# Audio.net
KiCad netlist of a schematic drawn in Altium Designer
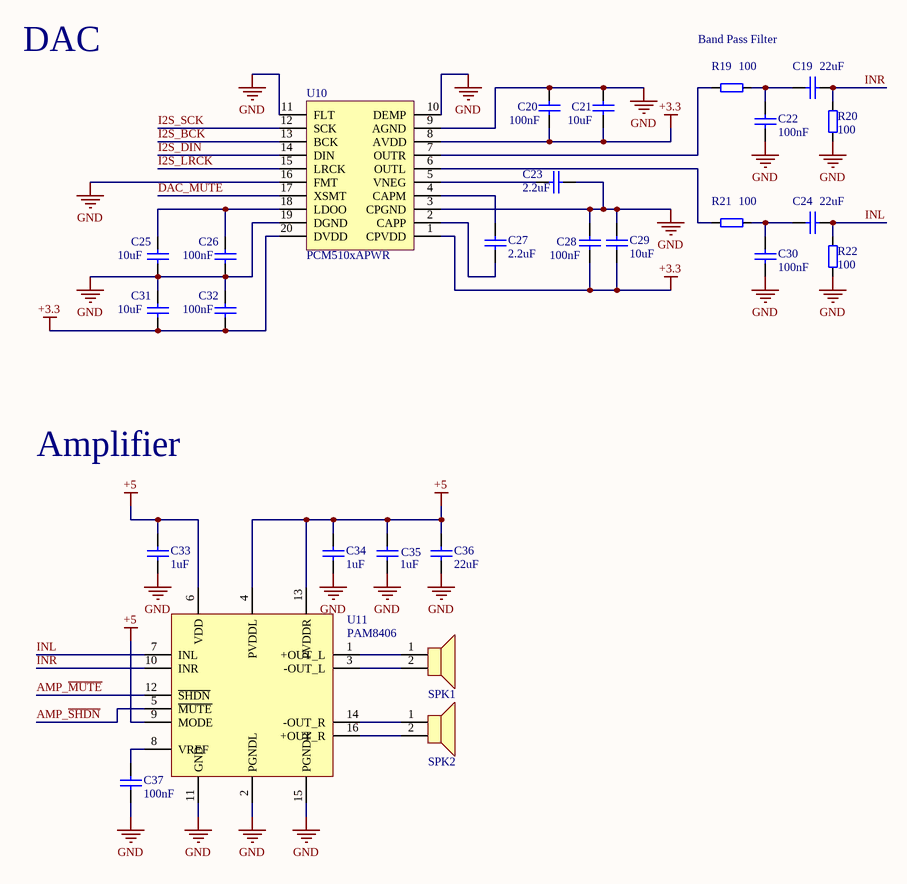
[diagram p0: Audio.SchDoc]

(export (version "E")
  (design (tool "Eeschema 10.0.6"))
  (components
    (comp (ref "C19")
      (value "Capacitor_22uF")
      (footprint "CAP 0805")
      (fields (field (name "CAPACITANCE") "22uF"))
      (libsource (lib "BasicComponents") (part "Capacitor_22uF"))
    )
    (comp (ref "C20")
      (value "Capacitor_100nF")
      (footprint "CAP 0805")
      (fields (field (name "CAPACITANCE") "100nF"))
      (libsource (lib "BasicComponents") (part "Capacitor_100nF"))
    )
    (comp (ref "C21")
      (value "Capacitor_10uF")
      (footprint "CAP 0805")
      (fields (field (name "CAPACITANCE") "10uF"))
      (libsource (lib "BasicComponents") (part "Capacitor_10uF"))
    )
    (comp (ref "C22")
      (value "Capacitor_100nF")
      (footprint "CAP 0805")
      (fields (field (name "CAPACITANCE") "100nF"))
      (libsource (lib "BasicComponents") (part "Capacitor_100nF"))
    )
    (comp (ref "C23")
      (value "Capacitor_2.2uF")
      (footprint "CAP 0805")
      (fields (field (name "CAPACITANCE") "2.2uF"))
      (libsource (lib "BasicComponents") (part "Capacitor_2.2uF"))
    )
    (comp (ref "C24")
      (value "Capacitor_22uF")
      (footprint "CAP 0805")
      (fields (field (name "CAPACITANCE") "22uF"))
      (libsource (lib "BasicComponents") (part "Capacitor_22uF"))
    )
    (comp (ref "C25")
      (value "Capacitor_10uF")
      (footprint "CAP 0805")
      (fields (field (name "CAPACITANCE") "10uF"))
      (libsource (lib "BasicComponents") (part "Capacitor_10uF"))
    )
    (comp (ref "C26")
      (value "Capacitor_100nF")
      (footprint "CAP 0805")
      (fields (field (name "CAPACITANCE") "100nF"))
      (libsource (lib "BasicComponents") (part "Capacitor_100nF"))
    )
    (comp (ref "C27")
      (value "Capacitor_2.2uF")
      (footprint "CAP 0805")
      (fields (field (name "CAPACITANCE") "2.2uF"))
      (libsource (lib "BasicComponents") (part "Capacitor_2.2uF"))
    )
    (comp (ref "C28")
      (value "Capacitor_100nF")
      (footprint "CAP 0805")
      (fields (field (name "CAPACITANCE") "100nF"))
      (libsource (lib "BasicComponents") (part "Capacitor_100nF"))
    )
    (comp (ref "C29")
      (value "Capacitor_10uF")
      (footprint "CAP 0805")
      (fields (field (name "CAPACITANCE") "10uF"))
      (libsource (lib "BasicComponents") (part "Capacitor_10uF"))
    )
    (comp (ref "C30")
      (value "Capacitor_100nF")
      (footprint "CAP 0805")
      (fields (field (name "CAPACITANCE") "100nF"))
      (libsource (lib "BasicComponents") (part "Capacitor_100nF"))
    )
    (comp (ref "C31")
      (value "Capacitor_10uF")
      (footprint "CAP 0805")
      (fields (field (name "CAPACITANCE") "10uF"))
      (libsource (lib "BasicComponents") (part "Capacitor_10uF"))
    )
    (comp (ref "C32")
      (value "Capacitor_100nF")
      (footprint "CAP 0805")
      (fields (field (name "CAPACITANCE") "100nF"))
      (libsource (lib "BasicComponents") (part "Capacitor_100nF"))
    )
    (comp (ref "C33")
      (value "Capacitor_1uF")
      (footprint "CAP 0805")
      (fields (field (name "CAPACITANCE") "1uF"))
      (libsource (lib "BasicComponents") (part "Capacitor_1uF"))
    )
    (comp (ref "C34")
      (value "Capacitor_1uF")
      (footprint "CAP 0805")
      (fields (field (name "CAPACITANCE") "1uF"))
      (libsource (lib "BasicComponents") (part "Capacitor_1uF"))
    )
    (comp (ref "C35")
      (value "Capacitor_1uF")
      (footprint "CAP 0805")
      (fields (field (name "CAPACITANCE") "1uF"))
      (libsource (lib "BasicComponents") (part "Capacitor_1uF"))
    )
    (comp (ref "C36")
      (value "Capacitor_22uF")
      (footprint "CAP 0805")
      (fields (field (name "CAPACITANCE") "22uF"))
      (libsource (lib "BasicComponents") (part "Capacitor_22uF"))
    )
    (comp (ref "C37")
      (value "Capacitor_100nF")
      (footprint "CAP 0805")
      (fields (field (name "CAPACITANCE") "100nF"))
      (libsource (lib "BasicComponents") (part "Capacitor_100nF"))
    )
    (comp (ref "R19")
      (value "Resistor_100")
      (footprint "RES 0805")
      (fields (field (name "RESISTANCE") "100"))
      (libsource (lib "") (part "Resistor_100_1"))
    )
    (comp (ref "R20")
      (value "Resistor_100")
      (footprint "RES 0805")
      (fields (field (name "RESISTANCE") "100"))
      (libsource (lib "BasicComponents") (part "Resistor_100"))
    )
    (comp (ref "R21")
      (value "Resistor_100")
      (footprint "RES 0805")
      (fields (field (name "RESISTANCE") "100"))
      (libsource (lib "") (part "Resistor_100_1"))
    )
    (comp (ref "R22")
      (value "Resistor_100")
      (footprint "RES 0805")
      (fields (field (name "RESISTANCE") "100"))
      (libsource (lib "BasicComponents") (part "Resistor_100"))
    )
    (comp (ref "SPK1")
      (value "Speaker")
      (footprint "2Pin")
      (libsource (lib "BasicComponents") (part "Speaker"))
    )
    (comp (ref "SPK2")
      (value "Speaker")
      (footprint "2Pin")
      (libsource (lib "BasicComponents") (part "Speaker"))
    )
    (comp (ref "U10")
      (value "PCM510xAPWR")
      (footprint "TSOP-20")
      (libsource (lib "CustomModule") (part "PCM510xAPWR"))
    )
    (comp (ref "U11")
      (value "PAM8406")
      (footprint "SOP-16N")
      (libsource (lib "CustomModule") (part "PAM8406"))
    )
  )
  (nets
    (net (code "1") (name "+3.3") (class "Default")
      (node (ref "C20") (pin "1") (pintype "passive"))
      (node (ref "C21") (pin "1") (pintype "passive"))
      (node (ref "C28") (pin "1") (pintype "passive"))
      (node (ref "C29") (pin "1") (pintype "passive"))
      (node (ref "C31") (pin "1") (pintype "passive"))
      (node (ref "C32") (pin "1") (pintype "passive"))
      (node (ref "U10") (pin "1") (pinfunction "CPVDD_1") (pintype "passive"))
      (node (ref "U10") (pin "20") (pinfunction "DVDD_20") (pintype "passive"))
      (node (ref "U10") (pin "8") (pinfunction "AVDD_8") (pintype "passive"))
    )
    (net (code "2") (name "+5") (class "Default")
      (node (ref "C33") (pin "2") (pintype "passive"))
      (node (ref "C34") (pin "2") (pintype "passive"))
      (node (ref "C35") (pin "2") (pintype "passive"))
      (node (ref "C36") (pin "2") (pintype "passive"))
      (node (ref "U11") (pin "13") (pinfunction "PVDDR_13") (pintype "passive"))
      (node (ref "U11") (pin "4") (pinfunction "PVDDL_4") (pintype "passive"))
      (node (ref "U11") (pin "6") (pinfunction "VDD_6") (pintype "passive"))
      (node (ref "U11") (pin "9") (pinfunction "MODE_9") (pintype "passive"))
    )
    (net (code "3") (name "/AMP_~{MUTE}") (class "Default")
      (node (ref "U11") (pin "12") (pinfunction "~{SHDN}_12") (pintype "passive"))
    )
    (net (code "4") (name "/AMP_~{SHDN}") (class "Default")
      (node (ref "U11") (pin "5") (pinfunction "~{MUTE}_5") (pintype "passive"))
    )
    (net (code "5") (name "/DAC_MUTE") (class "Default")
      (node (ref "U10") (pin "17") (pinfunction "XSMT_17") (pintype "passive"))
    )
    (net (code "6") (name "/I2S_BCK") (class "Default")
      (node (ref "U10") (pin "13") (pinfunction "BCK_13") (pintype "passive"))
    )
    (net (code "7") (name "/I2S_DIN") (class "Default")
      (node (ref "U10") (pin "14") (pinfunction "DIN_14") (pintype "passive"))
    )
    (net (code "8") (name "/I2S_LRCK") (class "Default")
      (node (ref "U10") (pin "15") (pinfunction "LRCK_15") (pintype "passive"))
    )
    (net (code "9") (name "/I2S_SCK") (class "Default")
      (node (ref "U10") (pin "12") (pinfunction "SCK_12") (pintype "passive"))
    )
    (net (code "10") (name "/INL") (class "Default")
      (node (ref "C24") (pin "2") (pintype "passive"))
      (node (ref "R22") (pin "2") (pintype "passive"))
      (node (ref "U11") (pin "7") (pinfunction "INL_7") (pintype "passive"))
    )
    (net (code "11") (name "/INR") (class "Default")
      (node (ref "C19") (pin "2") (pintype "passive"))
      (node (ref "R20") (pin "2") (pintype "passive"))
      (node (ref "U11") (pin "10") (pinfunction "INR_10") (pintype "passive"))
    )
    (net (code "12") (name "GND") (class "Default")
      (node (ref "C20") (pin "2") (pintype "passive"))
      (node (ref "C21") (pin "2") (pintype "passive"))
      (node (ref "C22") (pin "1") (pintype "passive"))
      (node (ref "C23") (pin "1") (pintype "passive"))
      (node (ref "C25") (pin "1") (pintype "passive"))
      (node (ref "C26") (pin "1") (pintype "passive"))
      (node (ref "C28") (pin "2") (pintype "passive"))
      (node (ref "C29") (pin "2") (pintype "passive"))
      (node (ref "C30") (pin "1") (pintype "passive"))
      (node (ref "C31") (pin "2") (pintype "passive"))
      (node (ref "C32") (pin "2") (pintype "passive"))
      (node (ref "C33") (pin "1") (pintype "passive"))
      (node (ref "C34") (pin "1") (pintype "passive"))
      (node (ref "C35") (pin "1") (pintype "passive"))
      (node (ref "C36") (pin "1") (pintype "passive"))
      (node (ref "C37") (pin "1") (pintype "passive"))
      (node (ref "R20") (pin "1") (pintype "passive"))
      (node (ref "R22") (pin "1") (pintype "passive"))
      (node (ref "U10") (pin "10") (pinfunction "DEMP_10") (pintype "passive"))
      (node (ref "U10") (pin "11") (pinfunction "FLT_11") (pintype "passive"))
      (node (ref "U10") (pin "16") (pinfunction "FMT_16") (pintype "passive"))
      (node (ref "U10") (pin "19") (pinfunction "DGND_19") (pintype "passive"))
      (node (ref "U10") (pin "3") (pinfunction "CPGND_3") (pintype "passive"))
      (node (ref "U10") (pin "9") (pinfunction "AGND_9") (pintype "passive"))
      (node (ref "U11") (pin "11") (pinfunction "GND_11") (pintype "passive"))
      (node (ref "U11") (pin "15") (pinfunction "PGNDR_15") (pintype "passive"))
      (node (ref "U11") (pin "2") (pinfunction "PGNDL_2") (pintype "passive"))
    )
    (net (code "13") (name "Net-(C19-Pad1)") (class "Default")
      (node (ref "C19") (pin "1") (pintype "passive"))
      (node (ref "C22") (pin "2") (pintype "passive"))
      (node (ref "R19") (pin "2") (pintype "passive"))
    )
    (net (code "14") (name "Net-(C24-Pad1)") (class "Default")
      (node (ref "C24") (pin "1") (pintype "passive"))
      (node (ref "C30") (pin "2") (pintype "passive"))
      (node (ref "R21") (pin "2") (pintype "passive"))
    )
    (net (code "15") (name "Net-(U10-CAPM)") (class "Default")
      (node (ref "C27") (pin "1") (pintype "passive"))
      (node (ref "U10") (pin "4") (pinfunction "CAPM_4") (pintype "passive"))
    )
    (net (code "16") (name "Net-(U10-CAPP)") (class "Default")
      (node (ref "C27") (pin "2") (pintype "passive"))
      (node (ref "U10") (pin "2") (pinfunction "CAPP_2") (pintype "passive"))
    )
    (net (code "17") (name "Net-(U10-LDOO)") (class "Default")
      (node (ref "C25") (pin "2") (pintype "passive"))
      (node (ref "C26") (pin "2") (pintype "passive"))
      (node (ref "U10") (pin "18") (pinfunction "LDOO_18") (pintype "passive"))
    )
    (net (code "18") (name "Net-(U10-OUTL)") (class "Default")
      (node (ref "R21") (pin "1") (pintype "passive"))
      (node (ref "U10") (pin "6") (pinfunction "OUTL_6") (pintype "passive"))
    )
    (net (code "19") (name "Net-(U10-OUTR)") (class "Default")
      (node (ref "R19") (pin "1") (pintype "passive"))
      (node (ref "U10") (pin "7") (pinfunction "OUTR_7") (pintype "passive"))
    )
    (net (code "20") (name "Net-(U10-VNEG)") (class "Default")
      (node (ref "C23") (pin "2") (pintype "passive"))
      (node (ref "U10") (pin "5") (pinfunction "VNEG_5") (pintype "passive"))
    )
    (net (code "21") (name "Net-(U11-+OUT_L)") (class "Default")
      (node (ref "SPK1") (pin "1") (pintype "passive"))
      (node (ref "U11") (pin "1") (pinfunction "+OUT_L_1") (pintype "passive"))
    )
    (net (code "22") (name "Net-(U11-+OUT_R)") (class "Default")
      (node (ref "SPK2") (pin "2") (pintype "passive"))
      (node (ref "U11") (pin "16") (pinfunction "+OUT_R_16") (pintype "passive"))
    )
    (net (code "23") (name "Net-(U11--OUT_L)") (class "Default")
      (node (ref "SPK1") (pin "2") (pintype "passive"))
      (node (ref "U11") (pin "3") (pinfunction "-OUT_L_3") (pintype "passive"))
    )
    (net (code "24") (name "Net-(U11--OUT_R)") (class "Default")
      (node (ref "SPK2") (pin "1") (pintype "passive"))
      (node (ref "U11") (pin "14") (pinfunction "-OUT_R_14") (pintype "passive"))
    )
    (net (code "25") (name "Net-(U11-VREF)") (class "Default")
      (node (ref "C37") (pin "2") (pintype "passive"))
      (node (ref "U11") (pin "8") (pinfunction "VREF_8") (pintype "passive"))
    )
  )
)
